# Main_module_v2.net
KiCad netlist of a schematic drawn in EAGLE
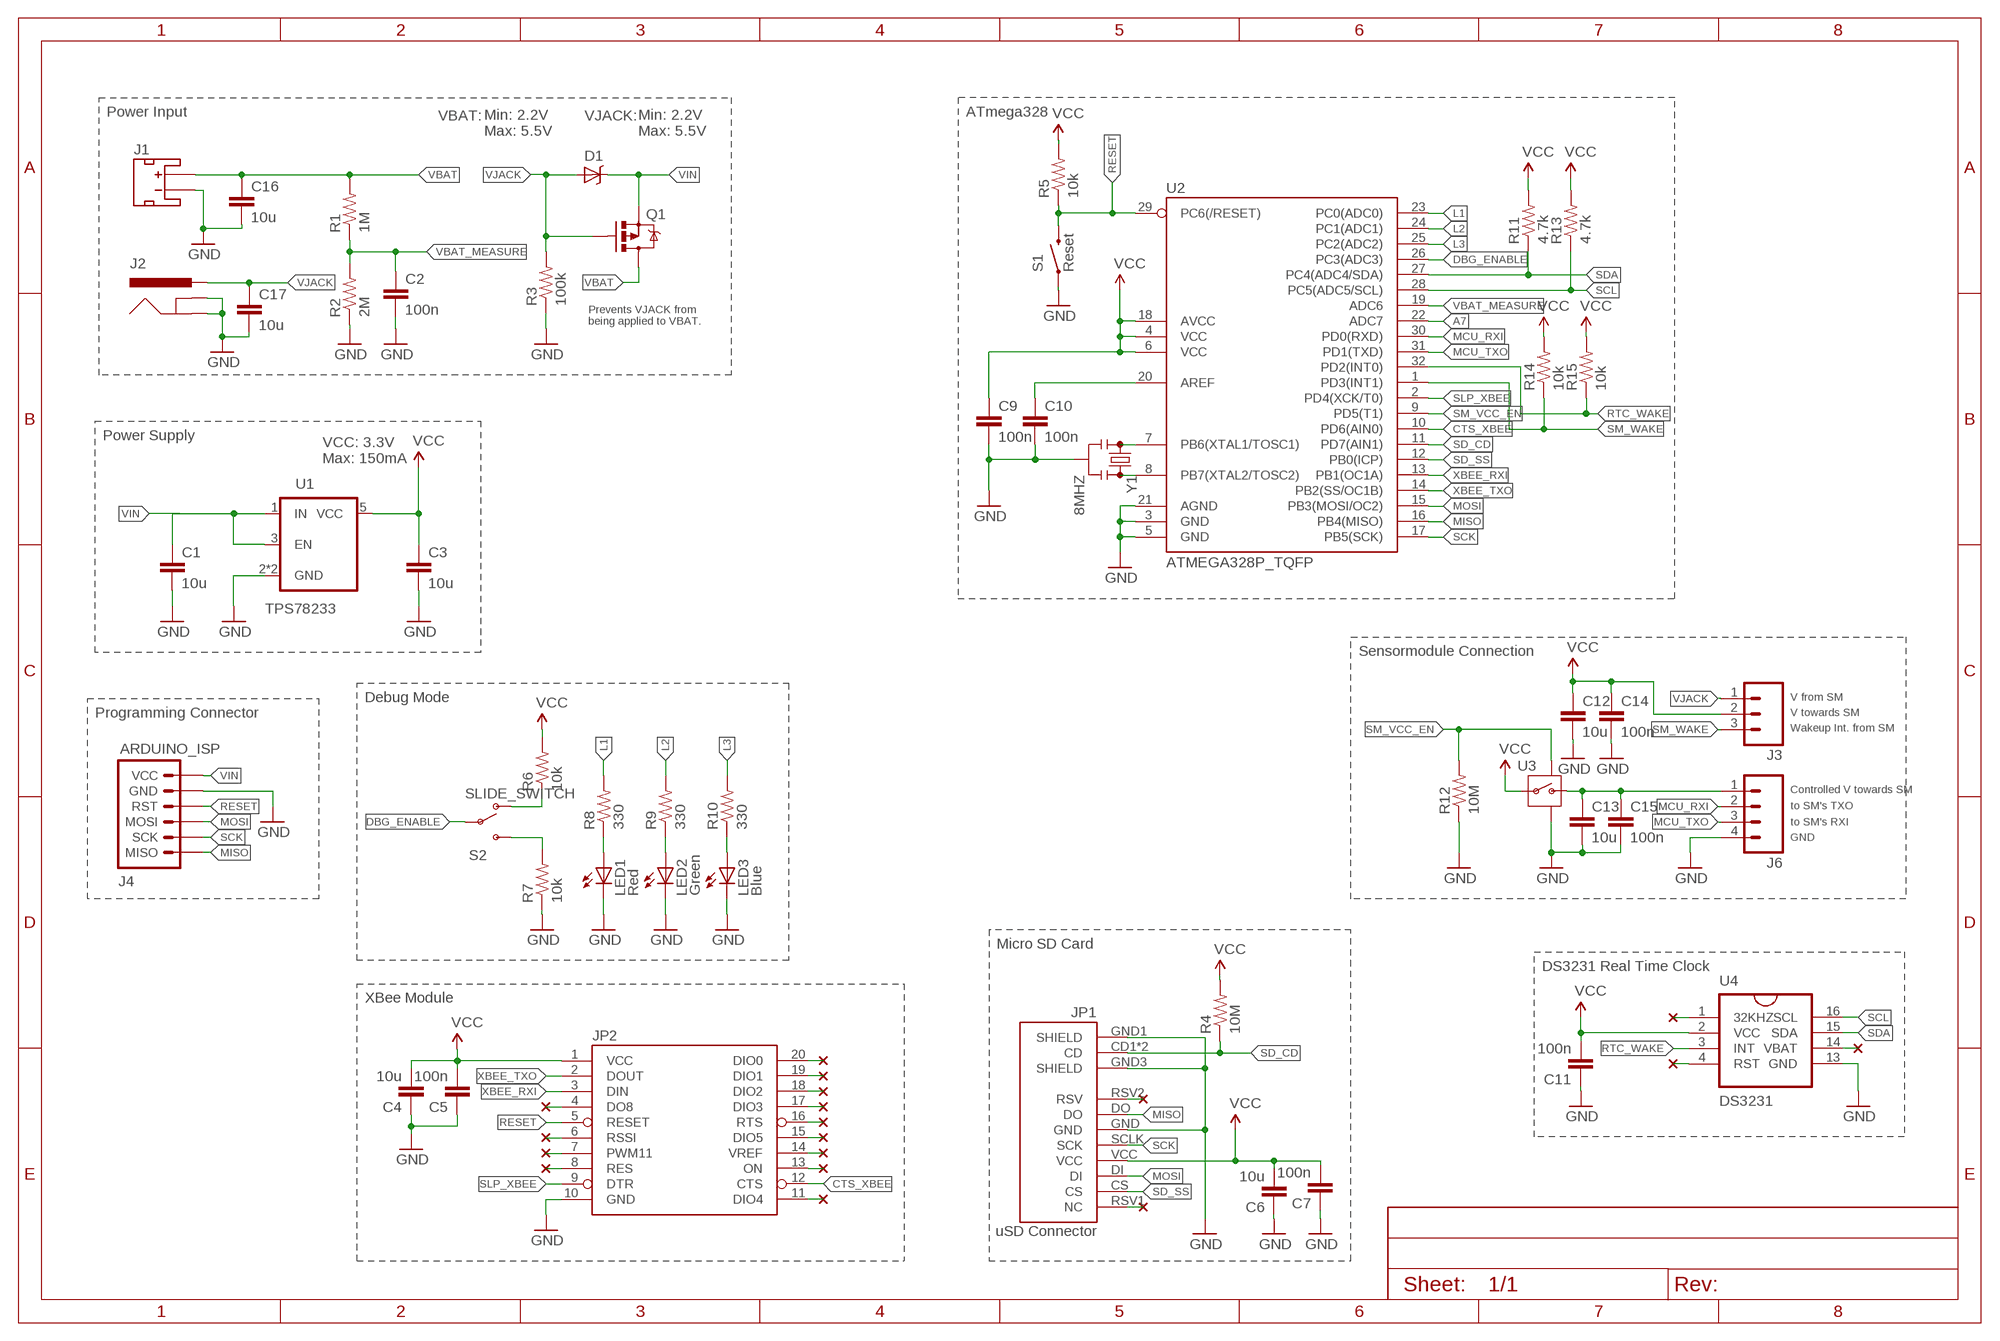
[diagram p0: schematic, sheet 1]

(export (version "E")
  (design (tool "Eeschema 10.0.6"))
  (components
    (comp (ref "C1")
      (value "10u")
      (footprint "eagle-import:C0805")
      (libsource (lib "eagle-import") (part "C"))
    )
    (comp (ref "C2")
      (value "100n")
      (footprint "eagle-import:C0805")
      (libsource (lib "eagle-import") (part "C"))
    )
    (comp (ref "C3")
      (value "10u")
      (footprint "eagle-import:C0805")
      (libsource (lib "eagle-import") (part "C"))
    )
    (comp (ref "C4")
      (value "10u")
      (footprint "eagle-import:C0805")
      (libsource (lib "eagle-import") (part "C"))
    )
    (comp (ref "C5")
      (value "100n")
      (footprint "eagle-import:C0805")
      (libsource (lib "eagle-import") (part "C"))
    )
    (comp (ref "C6")
      (value "10u")
      (footprint "eagle-import:C0805")
      (libsource (lib "eagle-import") (part "C"))
    )
    (comp (ref "C7")
      (value "100n")
      (footprint "eagle-import:C0805")
      (libsource (lib "eagle-import") (part "C"))
    )
    (comp (ref "C9")
      (value "100n")
      (footprint "eagle-import:C0805")
      (libsource (lib "eagle-import") (part "C"))
    )
    (comp (ref "C10")
      (value "100n")
      (footprint "eagle-import:C0805")
      (libsource (lib "eagle-import") (part "C"))
    )
    (comp (ref "C11")
      (value "100n")
      (footprint "eagle-import:C0805")
      (libsource (lib "eagle-import") (part "C"))
    )
    (comp (ref "C12")
      (value "10u")
      (footprint "eagle-import:C0805")
      (libsource (lib "eagle-import") (part "C"))
    )
    (comp (ref "C13")
      (value "10u")
      (footprint "eagle-import:C0805")
      (libsource (lib "eagle-import") (part "C"))
    )
    (comp (ref "C14")
      (value "100n")
      (footprint "eagle-import:C0805")
      (libsource (lib "eagle-import") (part "C"))
    )
    (comp (ref "C15")
      (value "100n")
      (footprint "eagle-import:C0805")
      (libsource (lib "eagle-import") (part "C"))
    )
    (comp (ref "C16")
      (value "10u")
      (footprint "eagle-import:C0805")
      (libsource (lib "eagle-import") (part "C"))
    )
    (comp (ref "C17")
      (value "10u")
      (footprint "eagle-import:C0805")
      (libsource (lib "eagle-import") (part "C"))
    )
    (comp (ref "D1")
      (value "DIODE-SCHOTTKY")
      (footprint "eagle-import:0603-DIODE")
      (libsource (lib "eagle-import") (part "DIODE-SCHOTTKY"))
    )
    (comp (ref "J1")
      (value "JST_2MM_MALE")
      (footprint "eagle-import:JST-2-SMD")
      (libsource (lib "eagle-import") (part "JST_2MM_MALE"))
    )
    (comp (ref "J2")
      (value "5.5x2.1mm Barrel")
      (footprint "eagle-import:POWER_JACK_SMD")
      (libsource (lib "eagle-import") (part "POWER_JACKSMD"))
    )
    (comp (ref "J3")
      (value "M03PTH")
      (footprint "eagle-import:1X03")
      (libsource (lib "eagle-import") (part "M03PTH"))
    )
    (comp (ref "J4")
      (value "ARDUINO_ISP")
      (footprint "eagle-import:M-2X3")
      (libsource (lib "eagle-import") (part "ARDUINO_ISP"))
    )
    (comp (ref "J6")
      (value "M04PTH")
      (footprint "eagle-import:1X04")
      (libsource (lib "eagle-import") (part "M04PTH"))
    )
    (comp (ref "JP1")
      (value "USD-SOCKETNEW")
      (footprint "eagle-import:MICRO-SD-SOCKET-PP")
      (libsource (lib "eagle-import") (part "USD-SOCKETNEW"))
    )
    (comp (ref "JP2")
      (value "XBEEB3")
      (footprint "eagle-import:XBEE-SMD")
      (libsource (lib "eagle-import") (part "XBEEB3"))
    )
    (comp (ref "LED1")
      (value "Red")
      (footprint "eagle-import:SML0805")
      (libsource (lib "eagle-import") (part "LEDSML0805"))
    )
    (comp (ref "LED2")
      (value "Green")
      (footprint "eagle-import:SML0805")
      (libsource (lib "eagle-import") (part "LEDSML0805"))
    )
    (comp (ref "LED3")
      (value "Blue")
      (footprint "eagle-import:SML0805")
      (libsource (lib "eagle-import") (part "LEDSML0805"))
    )
    (comp (ref "Q1")
      (value "PFET")
      (footprint "eagle-import:SOT23-3")
      (libsource (lib "eagle-import") (part "MOSFET-PCHANNELSMD"))
    )
    (comp (ref "R1")
      (value "1M")
      (footprint "eagle-import:0805")
      (libsource (lib "eagle-import") (part "RESISTOR0805-RES"))
    )
    (comp (ref "R2")
      (value "2M")
      (footprint "eagle-import:0805")
      (libsource (lib "eagle-import") (part "RESISTOR0805-RES"))
    )
    (comp (ref "R3")
      (value "100k")
      (footprint "eagle-import:0805")
      (libsource (lib "eagle-import") (part "RESISTOR0805-RES"))
    )
    (comp (ref "R4")
      (value "10M")
      (footprint "eagle-import:0805")
      (libsource (lib "eagle-import") (part "RESISTOR0805-RES"))
    )
    (comp (ref "R5")
      (value "10k")
      (footprint "eagle-import:0805")
      (libsource (lib "eagle-import") (part "RESISTOR0805-RES"))
    )
    (comp (ref "R6")
      (value "10k")
      (footprint "eagle-import:0805")
      (libsource (lib "eagle-import") (part "RESISTOR0805-RES"))
    )
    (comp (ref "R7")
      (value "10k")
      (footprint "eagle-import:0805")
      (libsource (lib "eagle-import") (part "RESISTOR0805-RES"))
    )
    (comp (ref "R8")
      (value "330")
      (footprint "eagle-import:0805")
      (libsource (lib "eagle-import") (part "RESISTOR0805-RES"))
    )
    (comp (ref "R9")
      (value "330")
      (footprint "eagle-import:0805")
      (libsource (lib "eagle-import") (part "RESISTOR0805-RES"))
    )
    (comp (ref "R10")
      (value "330")
      (footprint "eagle-import:0805")
      (libsource (lib "eagle-import") (part "RESISTOR0805-RES"))
    )
    (comp (ref "R11")
      (value "4.7k")
      (footprint "eagle-import:0805")
      (libsource (lib "eagle-import") (part "RESISTOR0805-RES"))
    )
    (comp (ref "R12")
      (value "10M")
      (footprint "eagle-import:0805")
      (libsource (lib "eagle-import") (part "RESISTOR0805-RES"))
    )
    (comp (ref "R13")
      (value "4.7k")
      (footprint "eagle-import:0805")
      (libsource (lib "eagle-import") (part "RESISTOR0805-RES"))
    )
    (comp (ref "R14")
      (value "10k")
      (footprint "eagle-import:0805")
      (libsource (lib "eagle-import") (part "RESISTOR0805-RES"))
    )
    (comp (ref "R15")
      (value "10k")
      (footprint "eagle-import:0805")
      (libsource (lib "eagle-import") (part "RESISTOR0805-RES"))
    )
    (comp (ref "S1")
      (value "Reset")
      (footprint "eagle-import:M-PUSHBUTTON-SMD")
      (libsource (lib "eagle-import") (part "PUSHBUTTON"))
    )
    (comp (ref "S2")
      (value "SLIDE_SWITCH")
      (footprint "eagle-import:P-JS202011SCQN")
      (libsource (lib "eagle-import") (part "SLIDE_SWITCH"))
    )
    (comp (ref "U1")
      (value "TPS78233")
      (footprint "eagle-import:SOT23-5")
      (libsource (lib "eagle-import") (part "TPS78233"))
    )
    (comp (ref "U2")
      (value "ATMEGA328P_TQFP")
      (footprint "eagle-import:TQFP32-08")
      (libsource (lib "eagle-import") (part "ATMEGA328P_TQFP"))
    )
    (comp (ref "U3")
      (value "SIP32431")
      (footprint "eagle-import:SC70")
      (libsource (lib "eagle-import") (part "SIP32431"))
    )
    (comp (ref "U4")
      (value "DS3231SOIC16")
      (footprint "eagle-import:SO016")
      (libsource (lib "eagle-import") (part "DS3231SOIC16"))
    )
    (comp (ref "Y1")
      (value "8MHZ")
      (footprint "eagle-import:RESONATOR-SMD")
      (libsource (lib "eagle-import") (part "RESONATOR8MHZ"))
    )
  )
  (nets
    (net (code "1") (name "A7") (class "Default")
      (node (ref "U2") (pin "22") (pinfunction "ADC7_22") (pintype "bidirectional"))
    )
    (net (code "2") (name "CTS_XBEE") (class "Default")
      (node (ref "JP2") (pin "12") (pinfunction "CTS_12") (pintype "output"))
      (node (ref "U2") (pin "10") (pinfunction "PD6(AIN0)_10") (pintype "bidirectional"))
    )
    (net (code "3") (name "DBG_ENABLE") (class "Default")
      (node (ref "S2") (pin "P$2") (pinfunction "MIDDLE_P$2") (pintype "passive"))
      (node (ref "S2") (pin "P$5") (pinfunction "MIDDLE_P$5") (pintype "passive"))
      (node (ref "U2") (pin "26") (pinfunction "PC3(ADC3)_26") (pintype "bidirectional"))
    )
    (net (code "4") (name "GND") (class "Default")
      (node (ref "C1") (pin "2") (pinfunction "2_2") (pintype "passive"))
      (node (ref "C10") (pin "2") (pinfunction "2_2") (pintype "passive"))
      (node (ref "C11") (pin "1") (pinfunction "1_1") (pintype "passive"))
      (node (ref "C12") (pin "2") (pinfunction "2_2") (pintype "passive"))
      (node (ref "C13") (pin "2") (pinfunction "2_2") (pintype "passive"))
      (node (ref "C14") (pin "2") (pinfunction "2_2") (pintype "passive"))
      (node (ref "C15") (pin "2") (pinfunction "2_2") (pintype "passive"))
      (node (ref "C16") (pin "2") (pinfunction "2_2") (pintype "passive"))
      (node (ref "C17") (pin "2") (pinfunction "2_2") (pintype "passive"))
      (node (ref "C2") (pin "2") (pinfunction "2_2") (pintype "passive"))
      (node (ref "C3") (pin "2") (pinfunction "2_2") (pintype "passive"))
      (node (ref "C4") (pin "1") (pinfunction "1_1") (pintype "passive"))
      (node (ref "C5") (pin "1") (pinfunction "1_1") (pintype "passive"))
      (node (ref "C6") (pin "1") (pinfunction "1_1") (pintype "passive"))
      (node (ref "C7") (pin "1") (pinfunction "1_1") (pintype "passive"))
      (node (ref "C9") (pin "2") (pinfunction "2_2") (pintype "passive"))
      (node (ref "J1") (pin "1") (pinfunction "-_1") (pintype "bidirectional"))
      (node (ref "J2") (pin "GND") (pinfunction "GNDBREAK_GND") (pintype "bidirectional"))
      (node (ref "J2") (pin "P$4") (pinfunction "GND_P$4") (pintype "bidirectional"))
      (node (ref "J4") (pin "P$5") (pinfunction "GND_P$5") (pintype "passive"))
      (node (ref "J6") (pin "4") (pinfunction "4_4") (pintype "passive"))
      (node (ref "JP1") (pin "GND") (pinfunction "GND_GND") (pintype "bidirectional"))
      (node (ref "JP1") (pin "GND1") (pinfunction "SHIELD_GND1") (pintype "bidirectional"))
      (node (ref "JP1") (pin "GND3") (pinfunction "SHIELD_GND3") (pintype "bidirectional"))
      (node (ref "JP2") (pin "10") (pinfunction "GND_10") (pintype "power_in"))
      (node (ref "LED1") (pin "C") (pinfunction "C_C") (pintype "passive"))
      (node (ref "LED2") (pin "C") (pinfunction "C_C") (pintype "passive"))
      (node (ref "LED3") (pin "C") (pinfunction "C_C") (pintype "passive"))
      (node (ref "R12") (pin "1") (pinfunction "1_1") (pintype "passive"))
      (node (ref "R2") (pin "1") (pinfunction "1_1") (pintype "passive"))
      (node (ref "R3") (pin "1") (pinfunction "1_1") (pintype "passive"))
      (node (ref "R7") (pin "1") (pinfunction "1_1") (pintype "passive"))
      (node (ref "S1") (pin "1") (pinfunction "LEFT_1") (pintype "passive"))
      (node (ref "S1") (pin "2") (pinfunction "LEFT_2") (pintype "passive"))
      (node (ref "U1") (pin "2") (pinfunction "GND_2") (pintype "input"))
      (node (ref "U1") (pin "4") (pinfunction "GND_4") (pintype "input"))
      (node (ref "U2") (pin "21") (pinfunction "AGND_21") (pintype "bidirectional"))
      (node (ref "U2") (pin "3") (pinfunction "GND_3") (pintype "bidirectional"))
      (node (ref "U2") (pin "5") (pinfunction "GND_5") (pintype "bidirectional"))
      (node (ref "U3") (pin "2") (pinfunction "GND_2") (pintype "passive"))
      (node (ref "U3") (pin "5") (pinfunction "GND_5") (pintype "passive"))
      (node (ref "U3") (pin "6") (pinfunction "GND_6") (pintype "passive"))
      (node (ref "U4") (pin "13") (pinfunction "GND_13") (pintype "bidirectional"))
      (node (ref "Y1") (pin "2") (pinfunction "2_2") (pintype "passive"))
    )
    (net (code "5") (name "L1") (class "Default")
      (node (ref "R8") (pin "2") (pinfunction "2_2") (pintype "passive"))
      (node (ref "U2") (pin "23") (pinfunction "PC0(ADC0)_23") (pintype "bidirectional"))
    )
    (net (code "6") (name "L2") (class "Default")
      (node (ref "R9") (pin "2") (pinfunction "2_2") (pintype "passive"))
      (node (ref "U2") (pin "24") (pinfunction "PC1(ADC1)_24") (pintype "bidirectional"))
    )
    (net (code "7") (name "L3") (class "Default")
      (node (ref "R10") (pin "2") (pinfunction "2_2") (pintype "passive"))
      (node (ref "U2") (pin "25") (pinfunction "PC2(ADC2)_25") (pintype "bidirectional"))
    )
    (net (code "8") (name "MCU_RXI") (class "Default")
      (node (ref "J6") (pin "2") (pinfunction "2_2") (pintype "passive"))
      (node (ref "U2") (pin "30") (pinfunction "PD0(RXD)_30") (pintype "bidirectional"))
    )
    (net (code "9") (name "MCU_TXO") (class "Default")
      (node (ref "J6") (pin "3") (pinfunction "3_3") (pintype "passive"))
      (node (ref "U2") (pin "31") (pinfunction "PD1(TXD)_31") (pintype "bidirectional"))
    )
    (net (code "10") (name "MISO") (class "Default")
      (node (ref "J4") (pin "P$1") (pinfunction "MISO_P$1") (pintype "passive"))
      (node (ref "JP1") (pin "DO") (pinfunction "DO_DO") (pintype "bidirectional"))
      (node (ref "U2") (pin "16") (pinfunction "PB4(MISO)_16") (pintype "bidirectional"))
    )
    (net (code "11") (name "MOSI") (class "Default")
      (node (ref "J4") (pin "P$3") (pinfunction "MOSI_P$3") (pintype "passive"))
      (node (ref "JP1") (pin "DI") (pinfunction "DI_DI") (pintype "bidirectional"))
      (node (ref "U2") (pin "15") (pinfunction "PB3(MOSI/OC2)_15") (pintype "bidirectional"))
    )
    (net (code "12") (name "Net-(LED1-PadA)") (class "Default")
      (node (ref "LED1") (pin "A") (pinfunction "A_A") (pintype "passive"))
      (node (ref "R8") (pin "1") (pinfunction "1_1") (pintype "passive"))
    )
    (net (code "13") (name "Net-(LED2-PadA)") (class "Default")
      (node (ref "LED2") (pin "A") (pinfunction "A_A") (pintype "passive"))
      (node (ref "R9") (pin "1") (pinfunction "1_1") (pintype "passive"))
    )
    (net (code "14") (name "Net-(LED3-PadA)") (class "Default")
      (node (ref "LED3") (pin "A") (pinfunction "A_A") (pintype "passive"))
      (node (ref "R10") (pin "1") (pinfunction "1_1") (pintype "passive"))
    )
    (net (code "15") (name "Net-(R6-Pad1)") (class "Default")
      (node (ref "R6") (pin "1") (pinfunction "1_1") (pintype "passive"))
      (node (ref "S2") (pin "P$3") (pinfunction "UPPER_P$3") (pintype "passive"))
      (node (ref "S2") (pin "P$6") (pinfunction "UPPER_P$6") (pintype "passive"))
    )
    (net (code "16") (name "Net-(R7-Pad2)") (class "Default")
      (node (ref "R7") (pin "2") (pinfunction "2_2") (pintype "passive"))
      (node (ref "S2") (pin "P$1") (pinfunction "LOWER_P$1") (pintype "passive"))
      (node (ref "S2") (pin "P$4") (pinfunction "LOWER_P$4") (pintype "passive"))
    )
    (net (code "17") (name "Net-(U2-AREF)") (class "Default")
      (node (ref "C10") (pin "1") (pinfunction "1_1") (pintype "passive"))
      (node (ref "U2") (pin "20") (pinfunction "AREF_20") (pintype "bidirectional"))
    )
    (net (code "18") (name "Net-(U2-PB6(XTAL1{slash}TOSC1))") (class "Default")
      (node (ref "U2") (pin "7") (pinfunction "PB6(XTAL1/TOSC1)_7") (pintype "bidirectional"))
      (node (ref "Y1") (pin "1") (pinfunction "1_1") (pintype "passive"))
    )
    (net (code "19") (name "Net-(U2-PB7(XTAL2{slash}TOSC2))") (class "Default")
      (node (ref "U2") (pin "8") (pinfunction "PB7(XTAL2/TOSC2)_8") (pintype "bidirectional"))
      (node (ref "Y1") (pin "3") (pinfunction "3_3") (pintype "passive"))
    )
    (net (code "20") (name "Net-(U3-OUT)") (class "Default")
      (node (ref "C13") (pin "1") (pinfunction "1_1") (pintype "passive"))
      (node (ref "C15") (pin "1") (pinfunction "1_1") (pintype "passive"))
      (node (ref "J6") (pin "1") (pinfunction "1_1") (pintype "passive"))
      (node (ref "U3") (pin "1") (pinfunction "OUT_1") (pintype "passive"))
    )
    (net (code "21") (name "RESET") (class "Default")
      (node (ref "J4") (pin "P$4") (pinfunction "RST_P$4") (pintype "passive"))
      (node (ref "JP2") (pin "5") (pinfunction "RESET_5") (pintype "input"))
      (node (ref "R5") (pin "1") (pinfunction "1_1") (pintype "passive"))
      (node (ref "S1") (pin "3") (pinfunction "RIGHT_3") (pintype "passive"))
      (node (ref "S1") (pin "4") (pinfunction "RIGHT_4") (pintype "passive"))
      (node (ref "U2") (pin "29") (pinfunction "PC6(/RESET)_29") (pintype "bidirectional"))
    )
    (net (code "22") (name "RTC_WAKE") (class "Default")
      (node (ref "R15") (pin "1") (pinfunction "1_1") (pintype "passive"))
      (node (ref "U2") (pin "32") (pinfunction "PD2(INT0)_32") (pintype "bidirectional"))
      (node (ref "U4") (pin "3") (pinfunction "INT_3") (pintype "bidirectional"))
    )
    (net (code "23") (name "SCK") (class "Default")
      (node (ref "J4") (pin "P$2") (pinfunction "SCK_P$2") (pintype "passive"))
      (node (ref "JP1") (pin "SCLK") (pinfunction "SCK_SCLK") (pintype "bidirectional"))
      (node (ref "U2") (pin "17") (pinfunction "PB5(SCK)_17") (pintype "bidirectional"))
    )
    (net (code "24") (name "SCL") (class "Default")
      (node (ref "R13") (pin "1") (pinfunction "1_1") (pintype "passive"))
      (node (ref "U2") (pin "28") (pinfunction "PC5(ADC5/SCL)_28") (pintype "bidirectional"))
      (node (ref "U4") (pin "16") (pinfunction "SCL_16") (pintype "bidirectional"))
    )
    (net (code "25") (name "SDA") (class "Default")
      (node (ref "R11") (pin "1") (pinfunction "1_1") (pintype "passive"))
      (node (ref "U2") (pin "27") (pinfunction "PC4(ADC4/SDA)_27") (pintype "bidirectional"))
      (node (ref "U4") (pin "15") (pinfunction "SDA_15") (pintype "bidirectional"))
    )
    (net (code "26") (name "SD_CD") (class "Default")
      (node (ref "JP1") (pin "CD1") (pinfunction "CD_CD1") (pintype "bidirectional"))
      (node (ref "JP1") (pin "CD2") (pinfunction "CD_CD2") (pintype "bidirectional"))
      (node (ref "R4") (pin "1") (pinfunction "1_1") (pintype "passive"))
      (node (ref "U2") (pin "11") (pinfunction "PD7(AIN1)_11") (pintype "bidirectional"))
    )
    (net (code "27") (name "SD_SS") (class "Default")
      (node (ref "JP1") (pin "CS") (pinfunction "CS_CS") (pintype "bidirectional"))
      (node (ref "U2") (pin "12") (pinfunction "PB0(ICP)_12") (pintype "bidirectional"))
    )
    (net (code "28") (name "SLP_XBEE") (class "Default")
      (node (ref "JP2") (pin "9") (pinfunction "DTR_9") (pintype "bidirectional"))
      (node (ref "U2") (pin "2") (pinfunction "PD4(XCK/T0)_2") (pintype "bidirectional"))
    )
    (net (code "29") (name "SM_VCC_EN") (class "Default")
      (node (ref "R12") (pin "2") (pinfunction "2_2") (pintype "passive"))
      (node (ref "U2") (pin "9") (pinfunction "PD5(T1)_9") (pintype "bidirectional"))
      (node (ref "U3") (pin "3") (pinfunction "ON_3") (pintype "passive"))
    )
    (net (code "30") (name "SM_WAKE") (class "Default")
      (node (ref "J3") (pin "3") (pinfunction "3_3") (pintype "passive"))
      (node (ref "R14") (pin "1") (pinfunction "1_1") (pintype "passive"))
      (node (ref "U2") (pin "1") (pinfunction "PD3(INT1)_1") (pintype "bidirectional"))
    )
    (net (code "31") (name "VBAT") (class "Default")
      (node (ref "C16") (pin "1") (pinfunction "1_1") (pintype "passive"))
      (node (ref "J1") (pin "2") (pinfunction "+_2") (pintype "bidirectional"))
      (node (ref "Q1") (pin "3") (pinfunction "D_3") (pintype "passive"))
      (node (ref "R1") (pin "2") (pinfunction "2_2") (pintype "passive"))
    )
    (net (code "32") (name "VBAT_MEASURE") (class "Default")
      (node (ref "C2") (pin "1") (pinfunction "1_1") (pintype "passive"))
      (node (ref "R1") (pin "1") (pinfunction "1_1") (pintype "passive"))
      (node (ref "R2") (pin "2") (pinfunction "2_2") (pintype "passive"))
      (node (ref "U2") (pin "19") (pinfunction "ADC6_19") (pintype "bidirectional"))
    )
    (net (code "33") (name "VCC") (class "Default")
      (node (ref "C11") (pin "2") (pinfunction "2_2") (pintype "passive"))
      (node (ref "C12") (pin "1") (pinfunction "1_1") (pintype "passive"))
      (node (ref "C14") (pin "1") (pinfunction "1_1") (pintype "passive"))
      (node (ref "C3") (pin "1") (pinfunction "1_1") (pintype "passive"))
      (node (ref "C4") (pin "2") (pinfunction "2_2") (pintype "passive"))
      (node (ref "C5") (pin "2") (pinfunction "2_2") (pintype "passive"))
      (node (ref "C6") (pin "2") (pinfunction "2_2") (pintype "passive"))
      (node (ref "C7") (pin "2") (pinfunction "2_2") (pintype "passive"))
      (node (ref "C9") (pin "1") (pinfunction "1_1") (pintype "passive"))
      (node (ref "J3") (pin "2") (pinfunction "2_2") (pintype "passive"))
      (node (ref "JP1") (pin "VCC") (pinfunction "VCC_VCC") (pintype "bidirectional"))
      (node (ref "JP2") (pin "1") (pinfunction "VCC_1") (pintype "power_in"))
      (node (ref "R11") (pin "2") (pinfunction "2_2") (pintype "passive"))
      (node (ref "R13") (pin "2") (pinfunction "2_2") (pintype "passive"))
      (node (ref "R14") (pin "2") (pinfunction "2_2") (pintype "passive"))
      (node (ref "R15") (pin "2") (pinfunction "2_2") (pintype "passive"))
      (node (ref "R4") (pin "2") (pinfunction "2_2") (pintype "passive"))
      (node (ref "R5") (pin "2") (pinfunction "2_2") (pintype "passive"))
      (node (ref "R6") (pin "2") (pinfunction "2_2") (pintype "passive"))
      (node (ref "U1") (pin "5") (pinfunction "VCC_5") (pintype "power_in"))
      (node (ref "U2") (pin "18") (pinfunction "AVCC_18") (pintype "bidirectional"))
      (node (ref "U2") (pin "4") (pinfunction "VCC_4") (pintype "bidirectional"))
      (node (ref "U2") (pin "6") (pinfunction "VCC_6") (pintype "bidirectional"))
      (node (ref "U3") (pin "4") (pinfunction "IN_4") (pintype "passive"))
      (node (ref "U4") (pin "2") (pinfunction "VCC_2") (pintype "bidirectional"))
    )
    (net (code "34") (name "VIN") (class "Default")
      (node (ref "C1") (pin "1") (pinfunction "1_1") (pintype "passive"))
      (node (ref "D1") (pin "C") (pinfunction "C_C") (pintype "passive"))
      (node (ref "J4") (pin "P$6") (pinfunction "VCC_P$6") (pintype "passive"))
      (node (ref "Q1") (pin "2") (pinfunction "S_2") (pintype "passive"))
      (node (ref "U1") (pin "1") (pinfunction "IN_1") (pintype "input"))
      (node (ref "U1") (pin "3") (pinfunction "EN_3") (pintype "input"))
    )
    (net (code "35") (name "VJACK") (class "Default")
      (node (ref "C17") (pin "1") (pinfunction "1_1") (pintype "passive"))
      (node (ref "D1") (pin "A") (pinfunction "A_A") (pintype "passive"))
      (node (ref "J2") (pin "VIN0") (pinfunction "PWR_VIN0") (pintype "bidirectional"))
      (node (ref "J2") (pin "VIN1") (pinfunction "PWR_VIN1") (pintype "bidirectional"))
      (node (ref "J3") (pin "1") (pinfunction "1_1") (pintype "passive"))
      (node (ref "Q1") (pin "1") (pinfunction "G_1") (pintype "passive"))
      (node (ref "R3") (pin "2") (pinfunction "2_2") (pintype "passive"))
    )
    (net (code "36") (name "XBEE_RXI") (class "Default")
      (node (ref "JP2") (pin "3") (pinfunction "DIN_3") (pintype "input"))
      (node (ref "U2") (pin "13") (pinfunction "PB1(OC1A)_13") (pintype "bidirectional"))
    )
    (net (code "37") (name "XBEE_TXO") (class "Default")
      (node (ref "JP2") (pin "2") (pinfunction "DOUT_2") (pintype "output"))
      (node (ref "U2") (pin "14") (pinfunction "PB2(SS/OC1B)_14") (pintype "bidirectional"))
    )
    (net (code "38") (name "unconnected-(J1-PAD1-PadNC1)") (class "Default")
      (node (ref "J1") (pin "NC1") (pinfunction "PAD1_NC1") (pintype "bidirectional"))
    )
    (net (code "39") (name "unconnected-(J1-PAD2-PadNC2)") (class "Default")
      (node (ref "J1") (pin "NC2") (pinfunction "PAD2_NC2") (pintype "bidirectional"))
    )
    (net (code "40") (name "unconnected-(JP1-NC-PadRSV1)") (class "Default")
      (node (ref "JP1") (pin "RSV1") (pinfunction "NC_RSV1") (pintype "bidirectional"))
    )
    (net (code "41") (name "unconnected-(JP1-RSV-PadRSV2)") (class "Default")
      (node (ref "JP1") (pin "RSV2") (pinfunction "RSV_RSV2") (pintype "bidirectional"))
    )
    (net (code "42") (name "unconnected-(JP2-DIO0-Pad20)") (class "Default")
      (node (ref "JP2") (pin "20") (pinfunction "DIO0_20") (pintype "bidirectional"))
    )
    (net (code "43") (name "unconnected-(JP2-DIO1-Pad19)") (class "Default")
      (node (ref "JP2") (pin "19") (pinfunction "DIO1_19") (pintype "bidirectional"))
    )
    (net (code "44") (name "unconnected-(JP2-DIO2-Pad18)") (class "Default")
      (node (ref "JP2") (pin "18") (pinfunction "DIO2_18") (pintype "bidirectional"))
    )
    (net (code "45") (name "unconnected-(JP2-DIO3-Pad17)") (class "Default")
      (node (ref "JP2") (pin "17") (pinfunction "DIO3_17") (pintype "bidirectional"))
    )
    (net (code "46") (name "unconnected-(JP2-DIO4-Pad11)") (class "Default")
      (node (ref "JP2") (pin "11") (pinfunction "DIO4_11") (pintype "bidirectional"))
    )
    (net (code "47") (name "unconnected-(JP2-DIO5-Pad15)") (class "Default")
      (node (ref "JP2") (pin "15") (pinfunction "DIO5_15") (pintype "bidirectional"))
    )
    (net (code "48") (name "unconnected-(JP2-DO8-Pad4)") (class "Default")
      (node (ref "JP2") (pin "4") (pinfunction "DO8_4") (pintype "bidirectional"))
    )
    (net (code "49") (name "unconnected-(JP2-ON-Pad13)") (class "Default")
      (node (ref "JP2") (pin "13") (pinfunction "ON_13") (pintype "bidirectional"))
    )
    (net (code "50") (name "unconnected-(JP2-PWM11-Pad7)") (class "Default")
      (node (ref "JP2") (pin "7") (pinfunction "PWM11_7") (pintype "bidirectional"))
    )
    (net (code "51") (name "unconnected-(JP2-RES-Pad8)") (class "Default")
      (node (ref "JP2") (pin "8") (pinfunction "RES_8") (pintype "bidirectional"))
    )
    (net (code "52") (name "unconnected-(JP2-RSSI-Pad6)") (class "Default")
      (node (ref "JP2") (pin "6") (pinfunction "RSSI_6") (pintype "bidirectional"))
    )
    (net (code "53") (name "unconnected-(JP2-RTS-Pad16)") (class "Default")
      (node (ref "JP2") (pin "16") (pinfunction "RTS_16") (pintype "input"))
    )
    (net (code "54") (name "unconnected-(JP2-VREF-Pad14)") (class "Default")
      (node (ref "JP2") (pin "14") (pinfunction "VREF_14") (pintype "bidirectional"))
    )
    (net (code "55") (name "unconnected-(U4-32KHZ-Pad1)") (class "Default")
      (node (ref "U4") (pin "1") (pinfunction "32KHZ_1") (pintype "bidirectional"))
    )
    (net (code "56") (name "unconnected-(U4-RST-Pad4)") (class "Default")
      (node (ref "U4") (pin "4") (pinfunction "RST_4") (pintype "bidirectional"))
    )
    (net (code "57") (name "unconnected-(U4-VBAT-Pad14)") (class "Default")
      (node (ref "U4") (pin "14") (pinfunction "VBAT_14") (pintype "bidirectional"))
    )
  )
)
